# Drone_v1.net
KiCad netlist of a schematic drawn in EAGLE
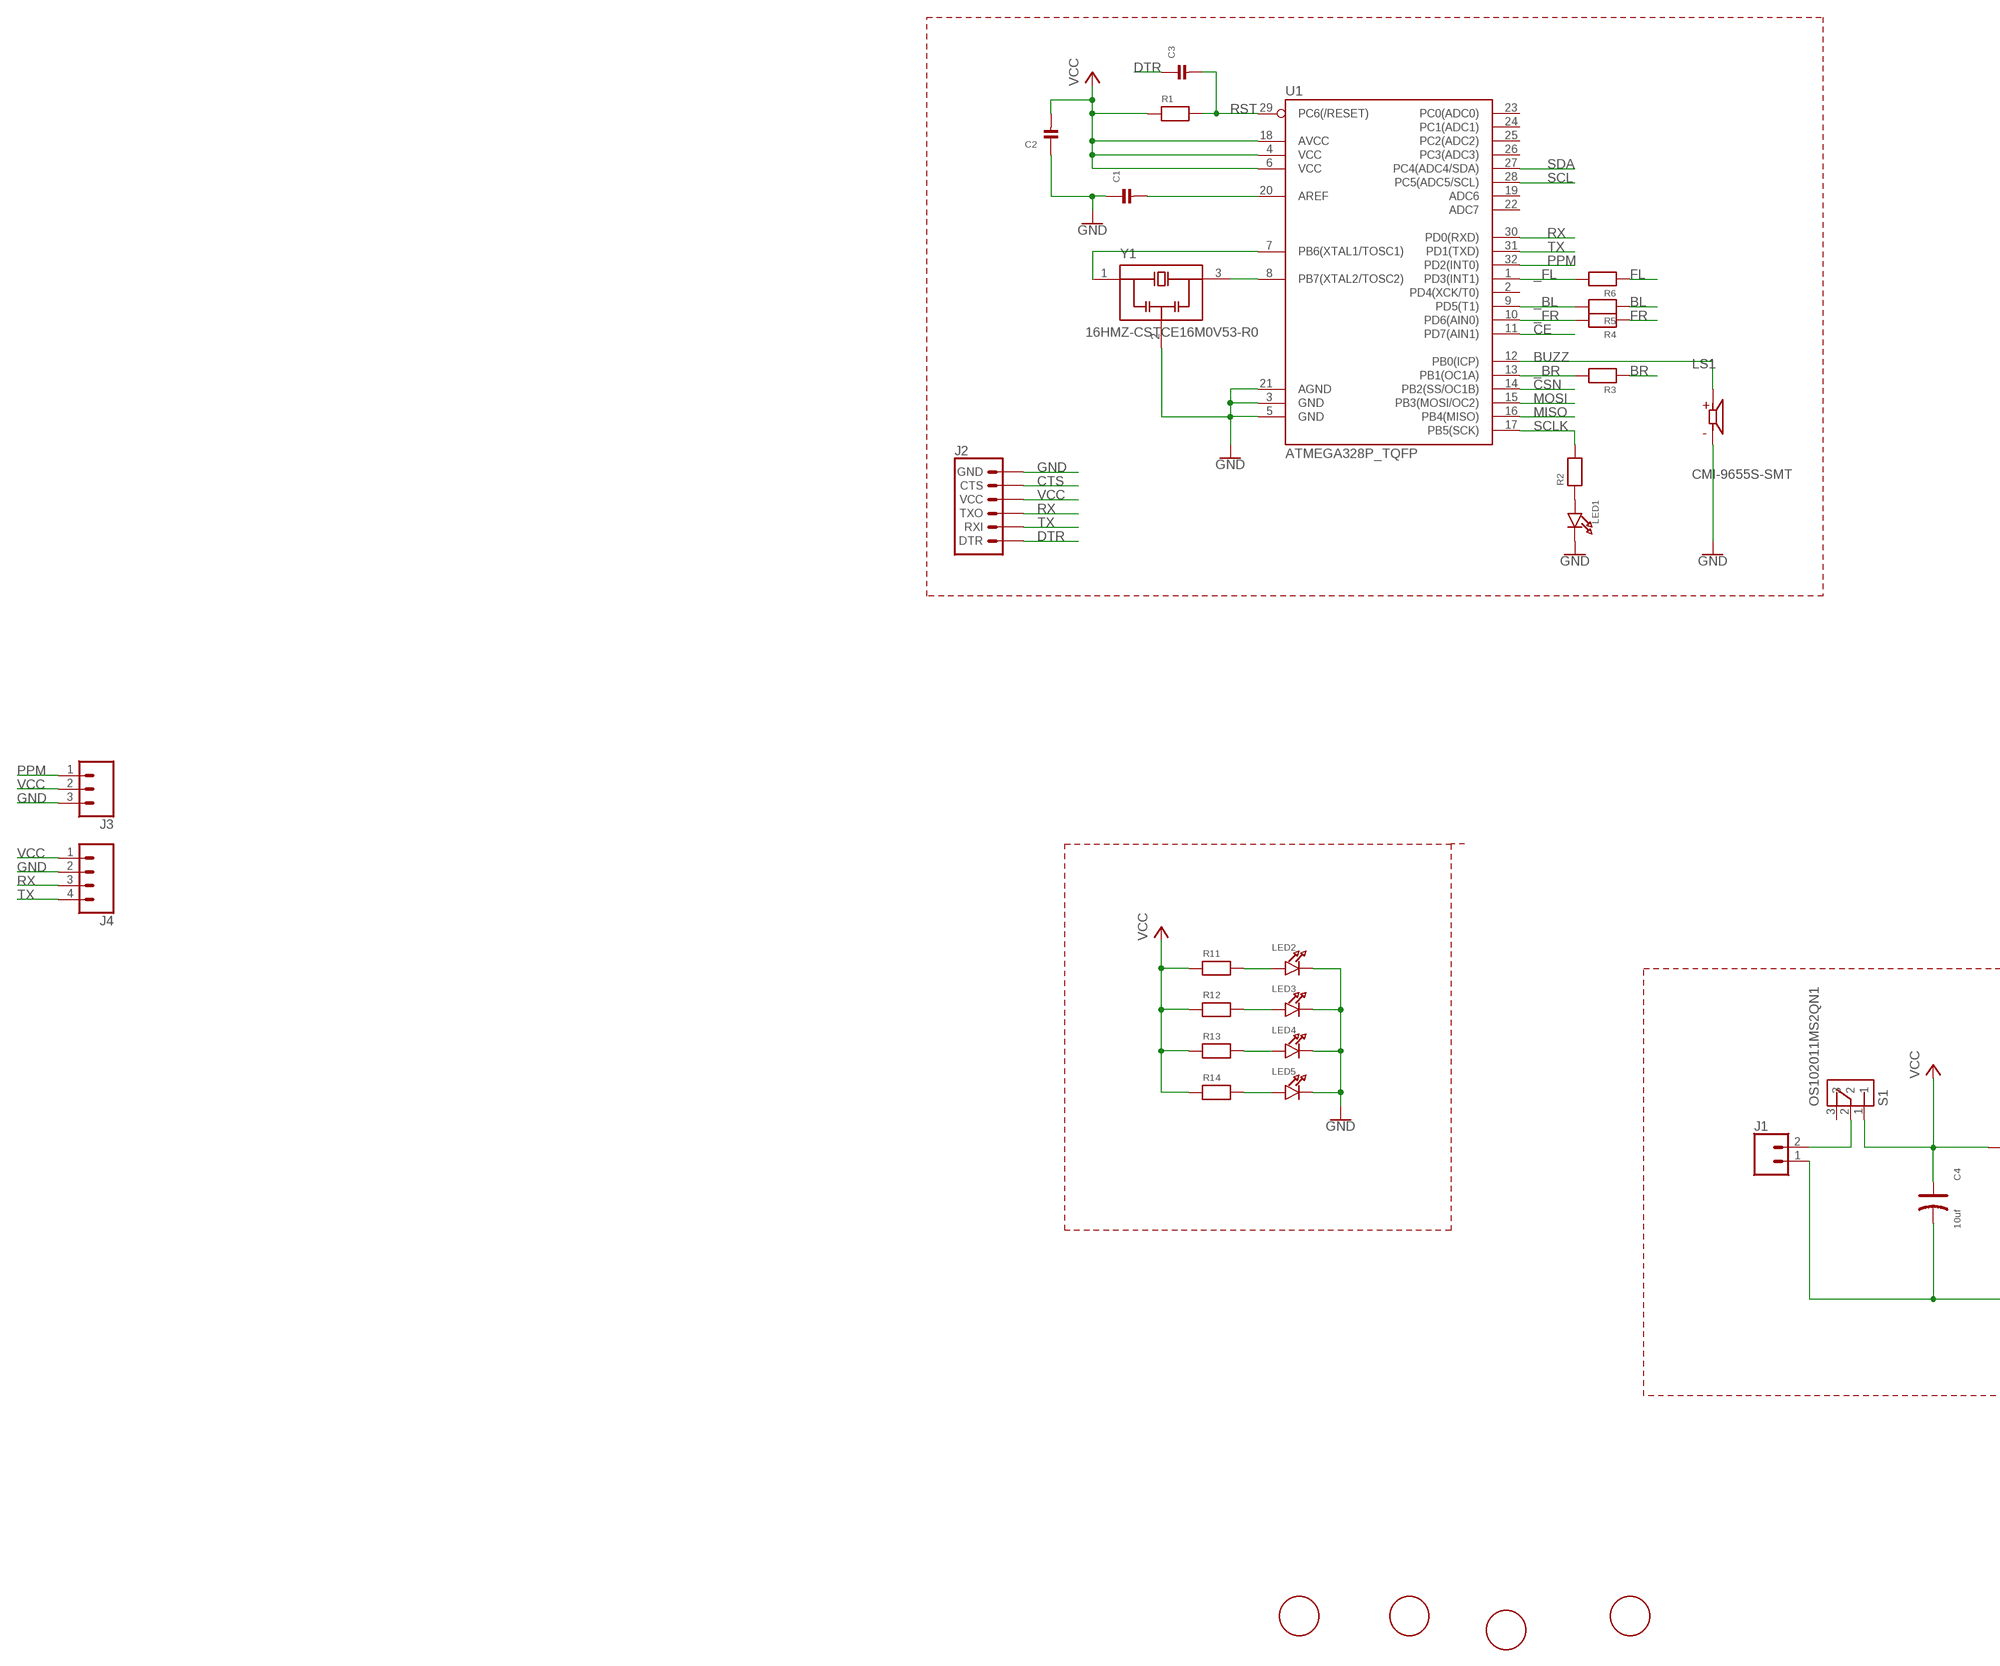
[diagram p0: schematic, sheet 1, part 1 of 2]
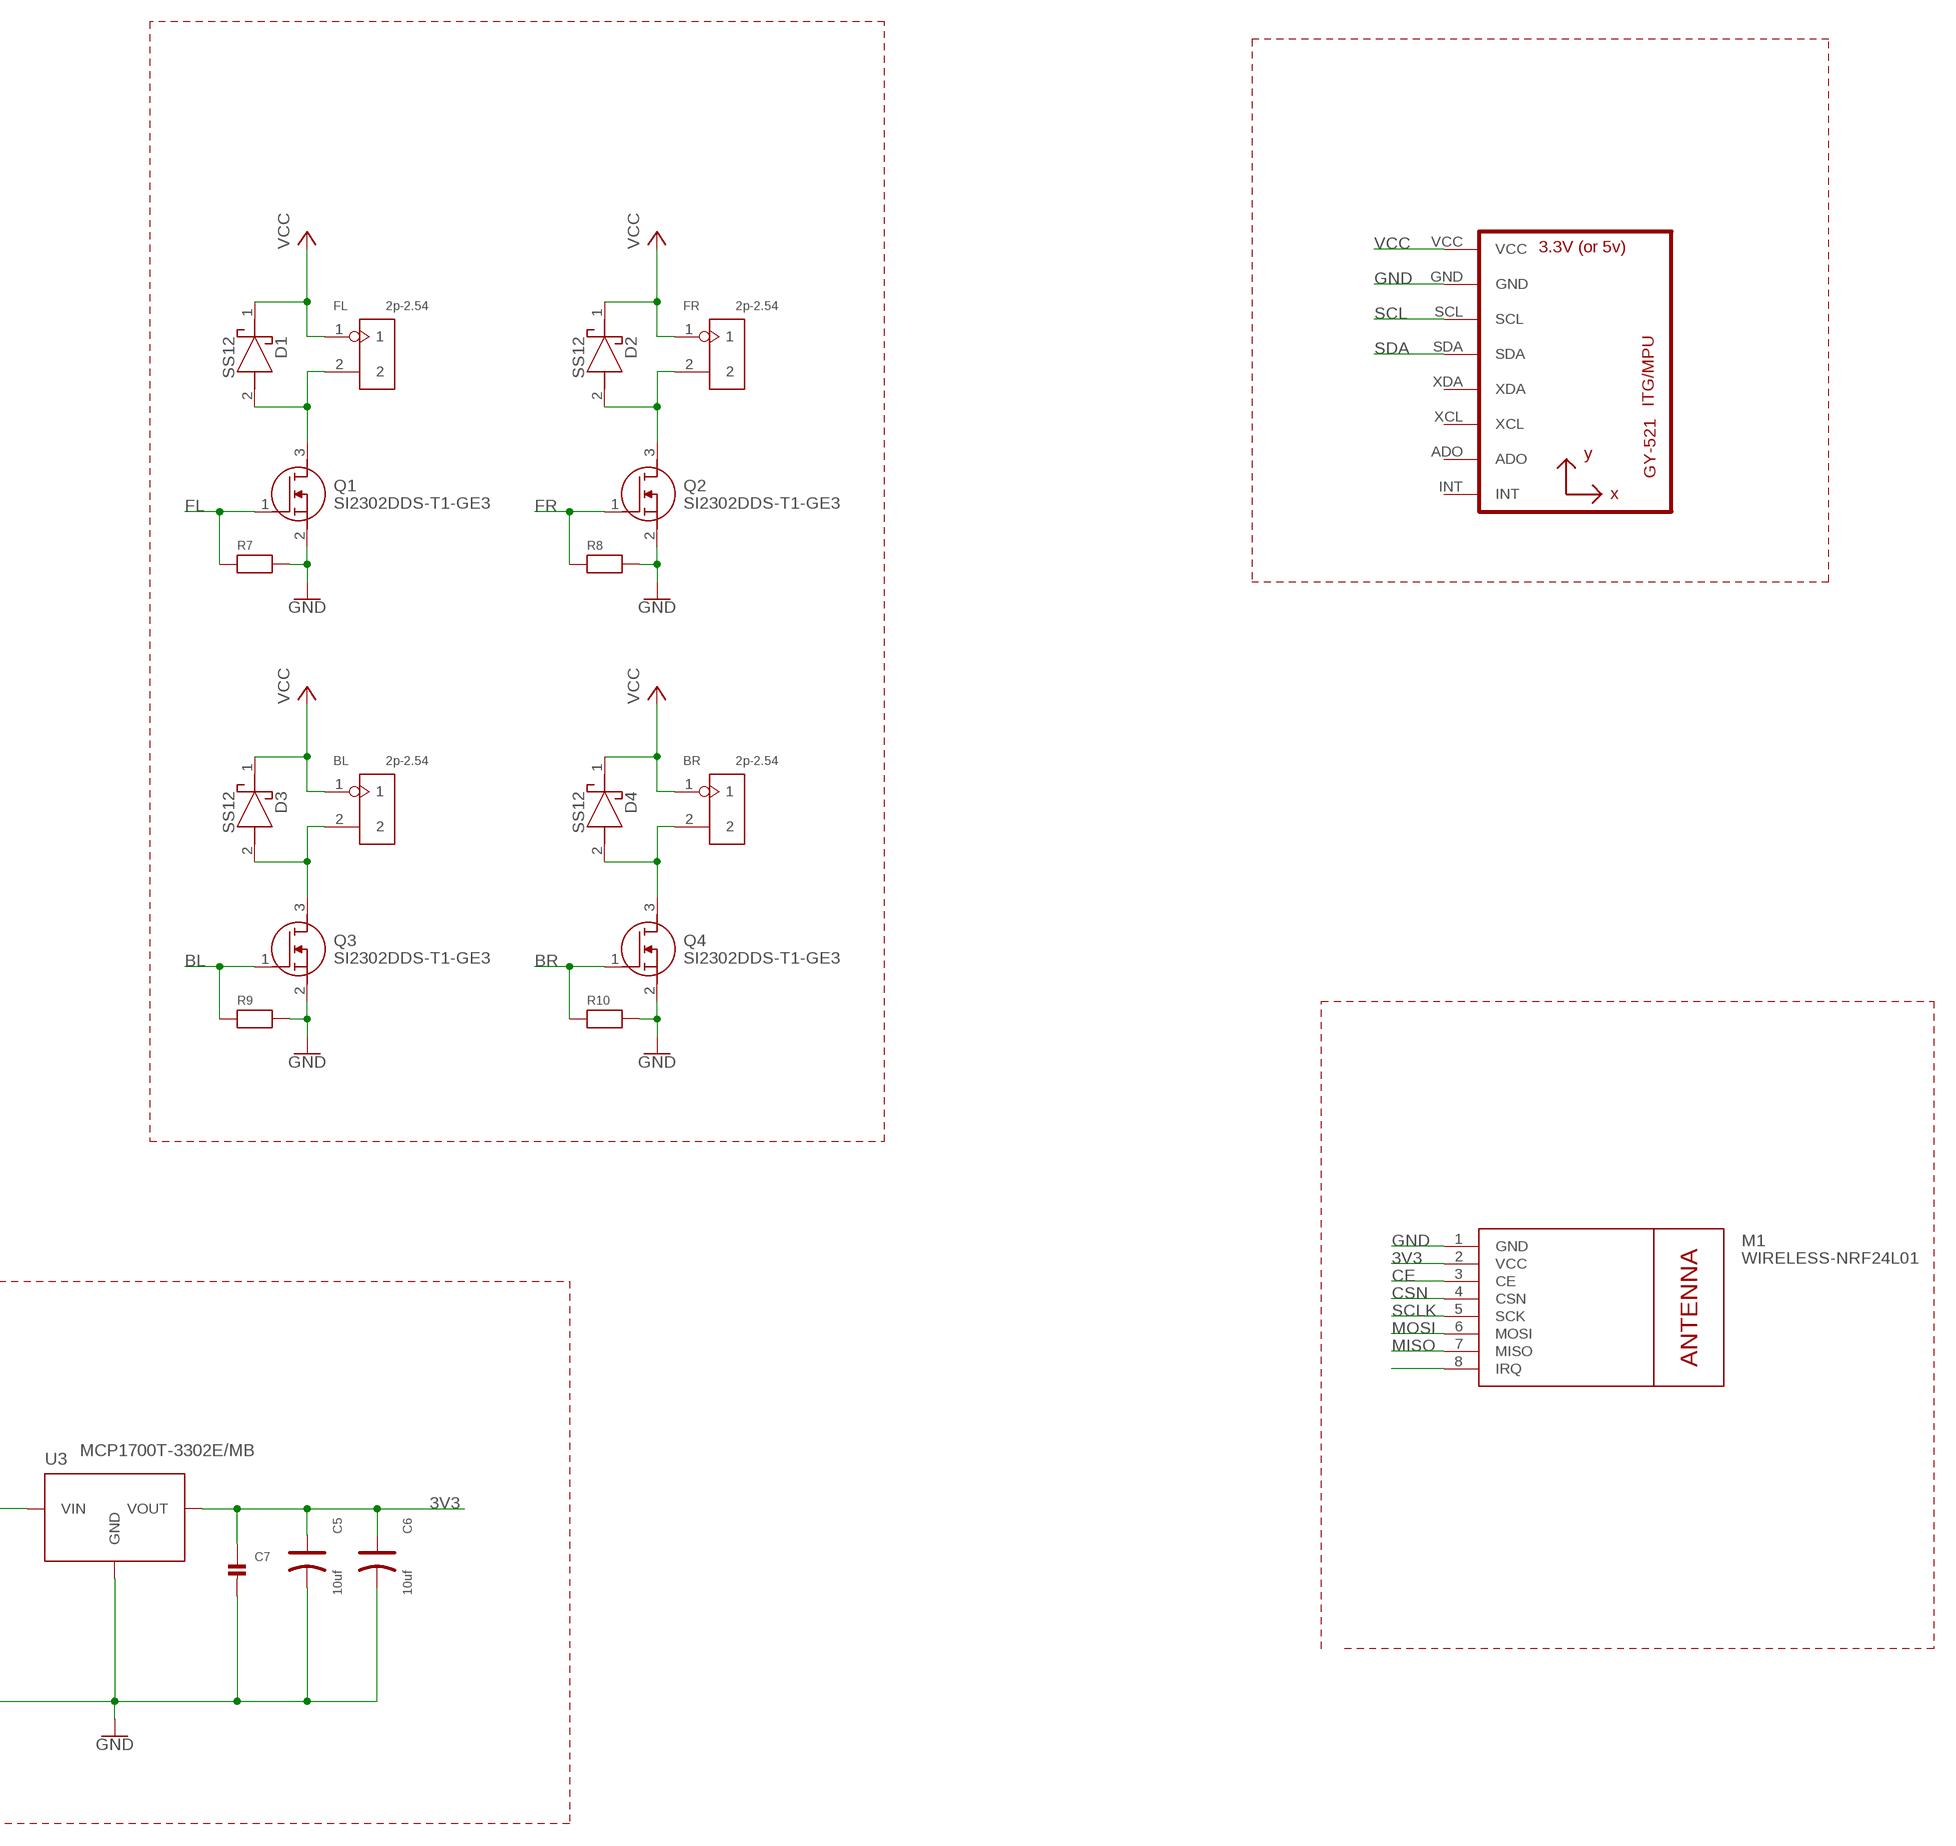
[diagram p1: schematic, sheet 1, part 2 of 2]

(export (version "E")
  (design (tool "Eeschema 10.0.6"))
  (components
    (comp (ref "BL")
      (value "2p-2.54")
      (footprint "eagle-import:H2-2.54-F")
      (fields (field (name "MPN") "F185-1102A1BSYA1"))
      (libsource (lib "eagle-import") (part "DIP-BLACK-FEMALE-HEADER-VERT(2P-2.54)"))
    )
    (comp (ref "BR")
      (value "2p-2.54")
      (footprint "eagle-import:H2-2.54-F")
      (fields (field (name "MPN") "F185-1102A1BSYA1"))
      (libsource (lib "eagle-import") (part "DIP-BLACK-FEMALE-HEADER-VERT(2P-2.54)"))
    )
    (comp (ref "C1")
      (value "CAP_CERAMIC0805")
      (footprint "eagle-import:C0805")
      (libsource (lib "eagle-import") (part "CAP_CERAMIC0805"))
    )
    (comp (ref "C2")
      (value "CAP_CERAMIC0805")
      (footprint "eagle-import:C0805")
      (libsource (lib "eagle-import") (part "CAP_CERAMIC0805"))
    )
    (comp (ref "C3")
      (value "CAP_CERAMIC0805")
      (footprint "eagle-import:C0805")
      (libsource (lib "eagle-import") (part "CAP_CERAMIC0805"))
    )
    (comp (ref "C4")
      (value "10uf")
      (footprint "eagle-import:AVX-A")
      (fields (field (name "MPN") "TAJA106K016RNJ"))
      (libsource (lib "eagle-import") (part "TANTALUM-SMD-10UF-16V-10%(AVX-A)"))
    )
    (comp (ref "C5")
      (value "10uf")
      (footprint "eagle-import:AVX-A")
      (fields (field (name "MPN") "TAJA106K016RNJ"))
      (libsource (lib "eagle-import") (part "TANTALUM-SMD-10UF-16V-10%(AVX-A)"))
    )
    (comp (ref "C6")
      (value "10uf")
      (footprint "eagle-import:AVX-A")
      (fields (field (name "MPN") "TAJA106K016RNJ"))
      (libsource (lib "eagle-import") (part "TANTALUM-SMD-10UF-16V-10%(AVX-A)"))
    )
    (comp (ref "C7")
      (value "CAP_CERAMIC0805")
      (footprint "eagle-import:C0805")
      (libsource (lib "eagle-import") (part "CAP_CERAMIC0805"))
    )
    (comp (ref "D1")
      (value "SS12")
      (footprint "eagle-import:DIOM5227X250N")
      (fields (field (name "MOUSER_PART_NUMBER") "512-SS12") (field (name "RS_PART_NUMBER") "9034428"))
      (libsource (lib "eagle-import") (part "SS12"))
    )
    (comp (ref "D2")
      (value "SS12")
      (footprint "eagle-import:DIOM5227X250N")
      (fields (field (name "MOUSER_PART_NUMBER") "512-SS12") (field (name "RS_PART_NUMBER") "9034428"))
      (libsource (lib "eagle-import") (part "SS12"))
    )
    (comp (ref "D3")
      (value "SS12")
      (footprint "eagle-import:DIOM5227X250N")
      (fields (field (name "MOUSER_PART_NUMBER") "512-SS12") (field (name "RS_PART_NUMBER") "9034428"))
      (libsource (lib "eagle-import") (part "SS12"))
    )
    (comp (ref "D4")
      (value "SS12")
      (footprint "eagle-import:DIOM5227X250N")
      (fields (field (name "MOUSER_PART_NUMBER") "512-SS12") (field (name "RS_PART_NUMBER") "9034428"))
      (libsource (lib "eagle-import") (part "SS12"))
    )
    (comp (ref "FL")
      (value "2p-2.54")
      (footprint "eagle-import:H2-2.54-F")
      (fields (field (name "MPN") "F185-1102A1BSYA1"))
      (libsource (lib "eagle-import") (part "DIP-BLACK-FEMALE-HEADER-VERT(2P-2.54)"))
    )
    (comp (ref "FR")
      (value "2p-2.54")
      (footprint "eagle-import:H2-2.54-F")
      (fields (field (name "MPN") "F185-1102A1BSYA1"))
      (libsource (lib "eagle-import") (part "DIP-BLACK-FEMALE-HEADER-VERT(2P-2.54)"))
    )
    (comp (ref "J1")
      (value "CONN_02-JST-2-PTH-NO_SILK")
      (footprint "eagle-import:JST-2-PTH-NS")
      (libsource (lib "eagle-import") (part "CONN_02-JST-2-PTH-NO_SILK"))
    )
    (comp (ref "J2")
      (value "6_PIN_SERIAL_TARGETSILK")
      (footprint "eagle-import:6_PIN_SERIAL_TARGET_SIDE_W_SILK")
      (libsource (lib "eagle-import") (part "6_PIN_SERIAL_TARGETSILK"))
    )
    (comp (ref "J3")
      (value "CONN_03")
      (footprint "eagle-import:1X03")
      (libsource (lib "eagle-import") (part "CONN_03"))
    )
    (comp (ref "J4")
      (value "CONN_04")
      (footprint "eagle-import:1X04")
      (libsource (lib "eagle-import") (part "CONN_04"))
    )
    (comp (ref "LED1")
      (value "LED0805_NOOUTLINE")
      (footprint "eagle-import:CHIPLED_0805_NOOUTLINE")
      (libsource (lib "eagle-import") (part "LED0805_NOOUTLINE"))
    )
    (comp (ref "LED2")
      (value "LED0805")
      (footprint "eagle-import:CHIPLED_0805")
      (libsource (lib "eagle-import") (part "LED0805"))
    )
    (comp (ref "LED3")
      (value "LED0805")
      (footprint "eagle-import:CHIPLED_0805")
      (libsource (lib "eagle-import") (part "LED0805"))
    )
    (comp (ref "LED4")
      (value "LED0805")
      (footprint "eagle-import:CHIPLED_0805")
      (libsource (lib "eagle-import") (part "LED0805"))
    )
    (comp (ref "LED5")
      (value "LED0805")
      (footprint "eagle-import:CHIPLED_0805")
      (libsource (lib "eagle-import") (part "LED0805"))
    )
    (comp (ref "LS1")
      (value "CMI-9655S-SMT")
      (footprint "eagle-import:CUI_CMI-9655S-SMT")
      (fields (field (name "MF") "CUI Devices") (field (name "MP") "CMI-9655S-SMT-TR"))
      (libsource (lib "eagle-import") (part "CMI-9655S-SMT"))
    )
    (comp (ref "M1")
      (value "WIRELESS-NRF24L01")
      (footprint "eagle-import:WIRELESS-NRF24L01")
      (libsource (lib "eagle-import") (part "WIRELESS-NRF24L01"))
    )
    (comp (ref "Q1")
      (value "SI2302DDS-T1-GE3")
      (footprint "eagle-import:SOT95P237X112-3N")
      (fields
        (field (name "MOUSER_PART_NUMBER") "78-SI2302DDS-T1-GE3")
        (field (name "RS_PART_NUMBER") "1526358P")
      )
      (libsource (lib "eagle-import") (part "SI2302DDS-T1-GE3"))
    )
    (comp (ref "Q2")
      (value "SI2302DDS-T1-GE3")
      (footprint "eagle-import:SOT95P237X112-3N")
      (fields
        (field (name "MOUSER_PART_NUMBER") "78-SI2302DDS-T1-GE3")
        (field (name "RS_PART_NUMBER") "1526358P")
      )
      (libsource (lib "eagle-import") (part "SI2302DDS-T1-GE3"))
    )
    (comp (ref "Q3")
      (value "SI2302DDS-T1-GE3")
      (footprint "eagle-import:SOT95P237X112-3N")
      (fields
        (field (name "MOUSER_PART_NUMBER") "78-SI2302DDS-T1-GE3")
        (field (name "RS_PART_NUMBER") "1526358P")
      )
      (libsource (lib "eagle-import") (part "SI2302DDS-T1-GE3"))
    )
    (comp (ref "Q4")
      (value "SI2302DDS-T1-GE3")
      (footprint "eagle-import:SOT95P237X112-3N")
      (fields
        (field (name "MOUSER_PART_NUMBER") "78-SI2302DDS-T1-GE3")
        (field (name "RS_PART_NUMBER") "1526358P")
      )
      (libsource (lib "eagle-import") (part "SI2302DDS-T1-GE3"))
    )
    (comp (ref "R1")
      (value "RESISTOR0805")
      (footprint "eagle-import:R0805")
      (libsource (lib "eagle-import") (part "RESISTOR0805"))
    )
    (comp (ref "R2")
      (value "RESISTOR0805")
      (footprint "eagle-import:R0805")
      (libsource (lib "eagle-import") (part "RESISTOR0805"))
    )
    (comp (ref "R3")
      (value "RESISTOR0805")
      (footprint "eagle-import:R0805")
      (libsource (lib "eagle-import") (part "RESISTOR0805"))
    )
    (comp (ref "R4")
      (value "RESISTOR0805")
      (footprint "eagle-import:R0805")
      (libsource (lib "eagle-import") (part "RESISTOR0805"))
    )
    (comp (ref "R5")
      (value "RESISTOR0805")
      (footprint "eagle-import:R0805")
      (libsource (lib "eagle-import") (part "RESISTOR0805"))
    )
    (comp (ref "R6")
      (value "RESISTOR0805")
      (footprint "eagle-import:R0805")
      (libsource (lib "eagle-import") (part "RESISTOR0805"))
    )
    (comp (ref "R7")
      (value "RESISTOR0805")
      (footprint "eagle-import:R0805")
      (libsource (lib "eagle-import") (part "RESISTOR0805"))
    )
    (comp (ref "R8")
      (value "RESISTOR0805")
      (footprint "eagle-import:R0805")
      (libsource (lib "eagle-import") (part "RESISTOR0805"))
    )
    (comp (ref "R9")
      (value "RESISTOR0805")
      (footprint "eagle-import:R0805")
      (libsource (lib "eagle-import") (part "RESISTOR0805"))
    )
    (comp (ref "R10")
      (value "RESISTOR0805")
      (footprint "eagle-import:R0805")
      (libsource (lib "eagle-import") (part "RESISTOR0805"))
    )
    (comp (ref "R11")
      (value "RESISTOR0805")
      (footprint "eagle-import:R0805")
      (libsource (lib "eagle-import") (part "RESISTOR0805"))
    )
    (comp (ref "R12")
      (value "RESISTOR0805")
      (footprint "eagle-import:R0805")
      (libsource (lib "eagle-import") (part "RESISTOR0805"))
    )
    (comp (ref "R13")
      (value "RESISTOR0805")
      (footprint "eagle-import:R0805")
      (libsource (lib "eagle-import") (part "RESISTOR0805"))
    )
    (comp (ref "R14")
      (value "RESISTOR0805")
      (footprint "eagle-import:R0805")
      (libsource (lib "eagle-import") (part "RESISTOR0805"))
    )
    (comp (ref "S1")
      (value "OS102011MS2QN1")
      (footprint "eagle-import:SW_OS102011MS2QN1")
      (fields (field (name "DIGI-KEY_PART_NUMBER") "CKN12284-ND") (field (name "MF") "C&K"))
      (libsource (lib "eagle-import") (part "OS102011MS2QN1"))
    )
    (comp (ref "U$1")
      (value "MICRO-DC-MOTOR-WITH-PROP")
      (footprint "eagle-import:MICRO-DC")
      (libsource (lib "eagle-import") (part "MICRO-DC-MOTOR-WITH-PROP"))
    )
    (comp (ref "U$2")
      (value "MICRO-DC-MOTOR-WITH-PROP")
      (footprint "eagle-import:MICRO-DC")
      (libsource (lib "eagle-import") (part "MICRO-DC-MOTOR-WITH-PROP"))
    )
    (comp (ref "U$3")
      (value "MICRO-DC-MOTOR-WITH-PROP")
      (footprint "eagle-import:MICRO-DC")
      (libsource (lib "eagle-import") (part "MICRO-DC-MOTOR-WITH-PROP"))
    )
    (comp (ref "U$4")
      (value "MICRO-DC-MOTOR-WITH-PROP")
      (footprint "eagle-import:MICRO-DC")
      (libsource (lib "eagle-import") (part "MICRO-DC-MOTOR-WITH-PROP"))
    )
    (comp (ref "U1")
      (value "ATMEGA328P_TQFP")
      (footprint "eagle-import:TQFP32-08")
      (libsource (lib "eagle-import") (part "ATMEGA328P_TQFP"))
    )
    (comp (ref "U2")
      (value "GY-521MPU6050")
      (footprint "eagle-import:GY-521")
      (libsource (lib "eagle-import") (part "GY-521MPU6050"))
    )
    (comp (ref "U3")
      (value "MCP1700T-3302E/MB")
      (footprint "eagle-import:MCP1700T-3302E_MB")
      (fields (field (name "MF") "Microchip"))
      (libsource (lib "eagle-import") (part "MCP1700T-3302E/MB"))
    )
    (comp (ref "Y1")
      (value "16HMZ-CSTCE16M0V53-R0")
      (footprint "eagle-import:OSC_CSTCE16M0V53-R0")
      (fields (field (name "MF") "Murata") (field (name "MP") "CSTCE16M0V53-R0"))
      (libsource (lib "eagle-import") (part "16HMZ-CSTCE16M0V53-R0"))
    )
  )
  (nets
    (net (code "1") (name "/3V3") (class "Default")
      (node (ref "C5") (pin "+") (pinfunction "+_+") (pintype "passive"))
      (node (ref "C6") (pin "+") (pinfunction "+_+") (pintype "passive"))
      (node (ref "C7") (pin "1") (pinfunction "P$1_1") (pintype "passive"))
      (node (ref "M1") (pin "2") (pinfunction "VCC_2") (pintype "power_in"))
      (node (ref "U3") (pin "3") (pinfunction "VOUT_3") (pintype "output"))
    )
    (net (code "2") (name "/BL") (class "Default")
      (node (ref "Q3") (pin "1") (pinfunction "G_1") (pintype "bidirectional"))
      (node (ref "R5") (pin "1") (pinfunction "1_1") (pintype "passive"))
      (node (ref "R9") (pin "1") (pinfunction "1_1") (pintype "passive"))
    )
    (net (code "3") (name "/BR") (class "Default")
      (node (ref "Q4") (pin "1") (pinfunction "G_1") (pintype "bidirectional"))
      (node (ref "R10") (pin "1") (pinfunction "1_1") (pintype "passive"))
      (node (ref "R3") (pin "1") (pinfunction "1_1") (pintype "passive"))
    )
    (net (code "4") (name "/BUZZ") (class "Default")
      (node (ref "LS1") (pin "P") (pinfunction "P_P") (pintype "passive"))
      (node (ref "U1") (pin "12") (pinfunction "PB0(ICP)_12") (pintype "bidirectional"))
    )
    (net (code "5") (name "/CE") (class "Default")
      (node (ref "M1") (pin "3") (pinfunction "CE_3") (pintype "bidirectional"))
      (node (ref "U1") (pin "11") (pinfunction "PD7(AIN1)_11") (pintype "bidirectional"))
    )
    (net (code "6") (name "/CSN") (class "Default")
      (node (ref "M1") (pin "4") (pinfunction "CSN_4") (pintype "bidirectional"))
      (node (ref "U1") (pin "14") (pinfunction "PB2(SS/OC1B)_14") (pintype "bidirectional"))
    )
    (net (code "7") (name "/CTS") (class "Default")
      (node (ref "J2") (pin "P$5") (pinfunction "CTS_P$5") (pintype "passive"))
    )
    (net (code "8") (name "/DTR") (class "Default")
      (node (ref "C3") (pin "1") (pinfunction "P$1_1") (pintype "passive"))
      (node (ref "J2") (pin "P$1") (pinfunction "DTR_P$1") (pintype "passive"))
    )
    (net (code "9") (name "/FL") (class "Default")
      (node (ref "Q1") (pin "1") (pinfunction "G_1") (pintype "bidirectional"))
      (node (ref "R6") (pin "1") (pinfunction "1_1") (pintype "passive"))
      (node (ref "R7") (pin "1") (pinfunction "1_1") (pintype "passive"))
    )
    (net (code "10") (name "/FR") (class "Default")
      (node (ref "Q2") (pin "1") (pinfunction "G_1") (pintype "bidirectional"))
      (node (ref "R4") (pin "1") (pinfunction "1_1") (pintype "passive"))
      (node (ref "R8") (pin "1") (pinfunction "1_1") (pintype "passive"))
    )
    (net (code "11") (name "/MISO") (class "Default")
      (node (ref "M1") (pin "7") (pinfunction "MISO_7") (pintype "bidirectional"))
      (node (ref "U1") (pin "16") (pinfunction "PB4(MISO)_16") (pintype "bidirectional"))
    )
    (net (code "12") (name "/MOSI") (class "Default")
      (node (ref "M1") (pin "6") (pinfunction "MOSI_6") (pintype "bidirectional"))
      (node (ref "U1") (pin "15") (pinfunction "PB3(MOSI/OC2)_15") (pintype "bidirectional"))
    )
    (net (code "13") (name "/PPM") (class "Default")
      (node (ref "J3") (pin "1") (pinfunction "1_1") (pintype "passive"))
      (node (ref "U1") (pin "32") (pinfunction "PD2(INT0)_32") (pintype "bidirectional"))
    )
    (net (code "14") (name "/RST") (class "Default")
      (node (ref "C3") (pin "2") (pinfunction "P$2_2") (pintype "passive"))
      (node (ref "R1") (pin "2") (pinfunction "2_2") (pintype "passive"))
      (node (ref "U1") (pin "29") (pinfunction "PC6(/RESET)_29") (pintype "bidirectional"))
    )
    (net (code "15") (name "/RX") (class "Default")
      (node (ref "J2") (pin "P$2") (pinfunction "TXO_P$2") (pintype "passive"))
      (node (ref "J4") (pin "3") (pinfunction "3_3") (pintype "passive"))
      (node (ref "U1") (pin "30") (pinfunction "PD0(RXD)_30") (pintype "bidirectional"))
    )
    (net (code "16") (name "/SCL") (class "Default")
      (node (ref "U1") (pin "28") (pinfunction "PC5(ADC5/SCL)_28") (pintype "bidirectional"))
      (node (ref "U2") (pin "SCL") (pinfunction "SCL_SCL") (pintype "bidirectional"))
    )
    (net (code "17") (name "/SCLK") (class "Default")
      (node (ref "M1") (pin "5") (pinfunction "SCK_5") (pintype "bidirectional"))
      (node (ref "R2") (pin "2") (pinfunction "2_2") (pintype "passive"))
      (node (ref "U1") (pin "17") (pinfunction "PB5(SCK)_17") (pintype "bidirectional"))
    )
    (net (code "18") (name "/SDA") (class "Default")
      (node (ref "U1") (pin "27") (pinfunction "PC4(ADC4/SDA)_27") (pintype "bidirectional"))
      (node (ref "U2") (pin "SDA") (pinfunction "SDA_SDA") (pintype "bidirectional"))
    )
    (net (code "19") (name "/TX") (class "Default")
      (node (ref "J2") (pin "P$3") (pinfunction "RXI_P$3") (pintype "passive"))
      (node (ref "J4") (pin "4") (pinfunction "4_4") (pintype "passive"))
      (node (ref "U1") (pin "31") (pinfunction "PD1(TXD)_31") (pintype "bidirectional"))
    )
    (net (code "20") (name "/_BL") (class "Default")
      (node (ref "R5") (pin "2") (pinfunction "2_2") (pintype "passive"))
      (node (ref "U1") (pin "9") (pinfunction "PD5(T1)_9") (pintype "bidirectional"))
    )
    (net (code "21") (name "/_BR") (class "Default")
      (node (ref "R3") (pin "2") (pinfunction "2_2") (pintype "passive"))
      (node (ref "U1") (pin "13") (pinfunction "PB1(OC1A)_13") (pintype "bidirectional"))
    )
    (net (code "22") (name "/_FL") (class "Default")
      (node (ref "R6") (pin "2") (pinfunction "2_2") (pintype "passive"))
      (node (ref "U1") (pin "1") (pinfunction "PD3(INT1)_1") (pintype "bidirectional"))
    )
    (net (code "23") (name "/_FR") (class "Default")
      (node (ref "R4") (pin "2") (pinfunction "2_2") (pintype "passive"))
      (node (ref "U1") (pin "10") (pinfunction "PD6(AIN0)_10") (pintype "bidirectional"))
    )
    (net (code "24") (name "GND") (class "Default")
      (node (ref "C1") (pin "1") (pinfunction "P$1_1") (pintype "passive"))
      (node (ref "C2") (pin "1") (pinfunction "P$1_1") (pintype "passive"))
      (node (ref "C4") (pin "-") (pinfunction "-_-") (pintype "passive"))
      (node (ref "C5") (pin "-") (pinfunction "-_-") (pintype "passive"))
      (node (ref "C6") (pin "-") (pinfunction "-_-") (pintype "passive"))
      (node (ref "C7") (pin "2") (pinfunction "P$2_2") (pintype "passive"))
      (node (ref "J1") (pin "1") (pinfunction "1_1") (pintype "passive"))
      (node (ref "J2") (pin "P$6") (pinfunction "GND_P$6") (pintype "passive"))
      (node (ref "J3") (pin "3") (pinfunction "3_3") (pintype "passive"))
      (node (ref "J4") (pin "2") (pinfunction "2_2") (pintype "passive"))
      (node (ref "LED1") (pin "C") (pinfunction "C_C") (pintype "passive"))
      (node (ref "LED2") (pin "C") (pinfunction "C_C") (pintype "passive"))
      (node (ref "LED3") (pin "C") (pinfunction "C_C") (pintype "passive"))
      (node (ref "LED4") (pin "C") (pinfunction "C_C") (pintype "passive"))
      (node (ref "LED5") (pin "C") (pinfunction "C_C") (pintype "passive"))
      (node (ref "LS1") (pin "N") (pinfunction "N_N") (pintype "passive"))
      (node (ref "M1") (pin "1") (pinfunction "GND_1") (pintype "power_in"))
      (node (ref "Q1") (pin "2") (pinfunction "S_2") (pintype "bidirectional"))
      (node (ref "Q2") (pin "2") (pinfunction "S_2") (pintype "bidirectional"))
      (node (ref "Q3") (pin "2") (pinfunction "S_2") (pintype "bidirectional"))
      (node (ref "Q4") (pin "2") (pinfunction "S_2") (pintype "bidirectional"))
      (node (ref "R10") (pin "2") (pinfunction "2_2") (pintype "passive"))
      (node (ref "R7") (pin "2") (pinfunction "2_2") (pintype "passive"))
      (node (ref "R8") (pin "2") (pinfunction "2_2") (pintype "passive"))
      (node (ref "R9") (pin "2") (pinfunction "2_2") (pintype "passive"))
      (node (ref "U1") (pin "21") (pinfunction "AGND_21") (pintype "bidirectional"))
      (node (ref "U1") (pin "3") (pinfunction "GND_3") (pintype "bidirectional"))
      (node (ref "U1") (pin "5") (pinfunction "GND_5") (pintype "bidirectional"))
      (node (ref "U2") (pin "GND") (pinfunction "GND_GND") (pintype "bidirectional"))
      (node (ref "U3") (pin "1") (pinfunction "GND_1") (pintype "power_in"))
      (node (ref "Y1") (pin "2") (pinfunction "GND_2") (pintype "power_in"))
    )
    (net (code "25") (name "Net-(C1-P$2)") (class "Default")
      (node (ref "C1") (pin "2") (pinfunction "P$2_2") (pintype "passive"))
      (node (ref "U1") (pin "20") (pinfunction "AREF_20") (pintype "bidirectional"))
    )
    (net (code "26") (name "Net-(D1-A)") (class "Default")
      (node (ref "D1") (pin "2") (pinfunction "A_2") (pintype "bidirectional"))
      (node (ref "FL") (pin "2") (pinfunction "2_2") (pintype "bidirectional"))
      (node (ref "Q1") (pin "3") (pinfunction "D_3") (pintype "bidirectional"))
    )
    (net (code "27") (name "Net-(D2-A)") (class "Default")
      (node (ref "D2") (pin "2") (pinfunction "A_2") (pintype "bidirectional"))
      (node (ref "FR") (pin "2") (pinfunction "2_2") (pintype "bidirectional"))
      (node (ref "Q2") (pin "3") (pinfunction "D_3") (pintype "bidirectional"))
    )
    (net (code "28") (name "Net-(D3-A)") (class "Default")
      (node (ref "BL") (pin "2") (pinfunction "2_2") (pintype "bidirectional"))
      (node (ref "D3") (pin "2") (pinfunction "A_2") (pintype "bidirectional"))
      (node (ref "Q3") (pin "3") (pinfunction "D_3") (pintype "bidirectional"))
    )
    (net (code "29") (name "Net-(D4-A)") (class "Default")
      (node (ref "BR") (pin "2") (pinfunction "2_2") (pintype "bidirectional"))
      (node (ref "D4") (pin "2") (pinfunction "A_2") (pintype "bidirectional"))
      (node (ref "Q4") (pin "3") (pinfunction "D_3") (pintype "bidirectional"))
    )
    (net (code "30") (name "Net-(J1-Pad2)") (class "Default")
      (node (ref "J1") (pin "2") (pinfunction "2_2") (pintype "passive"))
      (node (ref "S1") (pin "2") (pinfunction "2_2") (pintype "passive"))
    )
    (net (code "31") (name "Net-(LED1-PadA)") (class "Default")
      (node (ref "LED1") (pin "A") (pinfunction "A_A") (pintype "passive"))
      (node (ref "R2") (pin "1") (pinfunction "1_1") (pintype "passive"))
    )
    (net (code "32") (name "Net-(LED2-PadA)") (class "Default")
      (node (ref "LED2") (pin "A") (pinfunction "A_A") (pintype "passive"))
      (node (ref "R11") (pin "2") (pinfunction "2_2") (pintype "passive"))
    )
    (net (code "33") (name "Net-(LED3-PadA)") (class "Default")
      (node (ref "LED3") (pin "A") (pinfunction "A_A") (pintype "passive"))
      (node (ref "R12") (pin "2") (pinfunction "2_2") (pintype "passive"))
    )
    (net (code "34") (name "Net-(LED4-PadA)") (class "Default")
      (node (ref "LED4") (pin "A") (pinfunction "A_A") (pintype "passive"))
      (node (ref "R13") (pin "2") (pinfunction "2_2") (pintype "passive"))
    )
    (net (code "35") (name "Net-(LED5-PadA)") (class "Default")
      (node (ref "LED5") (pin "A") (pinfunction "A_A") (pintype "passive"))
      (node (ref "R14") (pin "2") (pinfunction "2_2") (pintype "passive"))
    )
    (net (code "36") (name "Net-(U1-PB6(XTAL1{slash}TOSC1))") (class "Default")
      (node (ref "U1") (pin "7") (pinfunction "PB6(XTAL1/TOSC1)_7") (pintype "bidirectional"))
      (node (ref "Y1") (pin "1") (pinfunction "IN_1") (pintype "input"))
    )
    (net (code "37") (name "Net-(U1-PB7(XTAL2{slash}TOSC2))") (class "Default")
      (node (ref "U1") (pin "8") (pinfunction "PB7(XTAL2/TOSC2)_8") (pintype "bidirectional"))
      (node (ref "Y1") (pin "3") (pinfunction "OUT_3") (pintype "output"))
    )
    (net (code "38") (name "VCC") (class "Default")
      (node (ref "BL") (pin "1") (pinfunction "1_1") (pintype "bidirectional"))
      (node (ref "BR") (pin "1") (pinfunction "1_1") (pintype "bidirectional"))
      (node (ref "C2") (pin "2") (pinfunction "P$2_2") (pintype "passive"))
      (node (ref "C4") (pin "+") (pinfunction "+_+") (pintype "passive"))
      (node (ref "D1") (pin "1") (pinfunction "K_1") (pintype "bidirectional"))
      (node (ref "D2") (pin "1") (pinfunction "K_1") (pintype "bidirectional"))
      (node (ref "D3") (pin "1") (pinfunction "K_1") (pintype "bidirectional"))
      (node (ref "D4") (pin "1") (pinfunction "K_1") (pintype "bidirectional"))
      (node (ref "FL") (pin "1") (pinfunction "1_1") (pintype "bidirectional"))
      (node (ref "FR") (pin "1") (pinfunction "1_1") (pintype "bidirectional"))
      (node (ref "J2") (pin "P$4") (pinfunction "VCC_P$4") (pintype "passive"))
      (node (ref "J3") (pin "2") (pinfunction "2_2") (pintype "passive"))
      (node (ref "J4") (pin "1") (pinfunction "1_1") (pintype "passive"))
      (node (ref "R1") (pin "1") (pinfunction "1_1") (pintype "passive"))
      (node (ref "R11") (pin "1") (pinfunction "1_1") (pintype "passive"))
      (node (ref "R12") (pin "1") (pinfunction "1_1") (pintype "passive"))
      (node (ref "R13") (pin "1") (pinfunction "1_1") (pintype "passive"))
      (node (ref "R14") (pin "1") (pinfunction "1_1") (pintype "passive"))
      (node (ref "S1") (pin "1") (pinfunction "1_1") (pintype "passive"))
      (node (ref "U1") (pin "18") (pinfunction "AVCC_18") (pintype "bidirectional"))
      (node (ref "U1") (pin "4") (pinfunction "VCC_4") (pintype "bidirectional"))
      (node (ref "U1") (pin "6") (pinfunction "VCC_6") (pintype "bidirectional"))
      (node (ref "U2") (pin "VCC") (pinfunction "VCC_VCC") (pintype "bidirectional"))
      (node (ref "U3") (pin "2") (pinfunction "VIN_2") (pintype "input"))
      (node (ref "U3") (pin "2.1") (pinfunction "VIN_2.1") (pintype "input"))
    )
    (net (code "39") (name "unconnected-(M1-IRQ-Pad8)") (class "Default")
      (node (ref "M1") (pin "8") (pinfunction "IRQ_8") (pintype "bidirectional"))
    )
    (net (code "40") (name "unconnected-(S1-Pad3)") (class "Default")
      (node (ref "S1") (pin "3") (pinfunction "3_3") (pintype "passive"))
    )
    (net (code "41") (name "unconnected-(U1-ADC6-Pad19)") (class "Default")
      (node (ref "U1") (pin "19") (pinfunction "ADC6_19") (pintype "bidirectional"))
    )
    (net (code "42") (name "unconnected-(U1-ADC7-Pad22)") (class "Default")
      (node (ref "U1") (pin "22") (pinfunction "ADC7_22") (pintype "bidirectional"))
    )
    (net (code "43") (name "unconnected-(U1-PC0(ADC0)-Pad23)") (class "Default")
      (node (ref "U1") (pin "23") (pinfunction "PC0(ADC0)_23") (pintype "bidirectional"))
    )
    (net (code "44") (name "unconnected-(U1-PC1(ADC1)-Pad24)") (class "Default")
      (node (ref "U1") (pin "24") (pinfunction "PC1(ADC1)_24") (pintype "bidirectional"))
    )
    (net (code "45") (name "unconnected-(U1-PC2(ADC2)-Pad25)") (class "Default")
      (node (ref "U1") (pin "25") (pinfunction "PC2(ADC2)_25") (pintype "bidirectional"))
    )
    (net (code "46") (name "unconnected-(U1-PC3(ADC3)-Pad26)") (class "Default")
      (node (ref "U1") (pin "26") (pinfunction "PC3(ADC3)_26") (pintype "bidirectional"))
    )
    (net (code "47") (name "unconnected-(U1-PD4(XCK{slash}T0)-Pad2)") (class "Default")
      (node (ref "U1") (pin "2") (pinfunction "PD4(XCK/T0)_2") (pintype "bidirectional"))
    )
    (net (code "48") (name "unconnected-(U2-PadADO)") (class "Default")
      (node (ref "U2") (pin "ADO") (pinfunction "ADO_ADO") (pintype "bidirectional"))
    )
    (net (code "49") (name "unconnected-(U2-PadINT)") (class "Default")
      (node (ref "U2") (pin "INT") (pinfunction "INT_INT") (pintype "bidirectional"))
    )
    (net (code "50") (name "unconnected-(U2-PadXCL)") (class "Default")
      (node (ref "U2") (pin "XCL") (pinfunction "XCL_XCL") (pintype "bidirectional"))
    )
    (net (code "51") (name "unconnected-(U2-PadXDA)") (class "Default")
      (node (ref "U2") (pin "XDA") (pinfunction "XDA_XDA") (pintype "bidirectional"))
    )
  )
)
